# numeric.net
KiCad netlist of a schematic drawn in Altium Designer
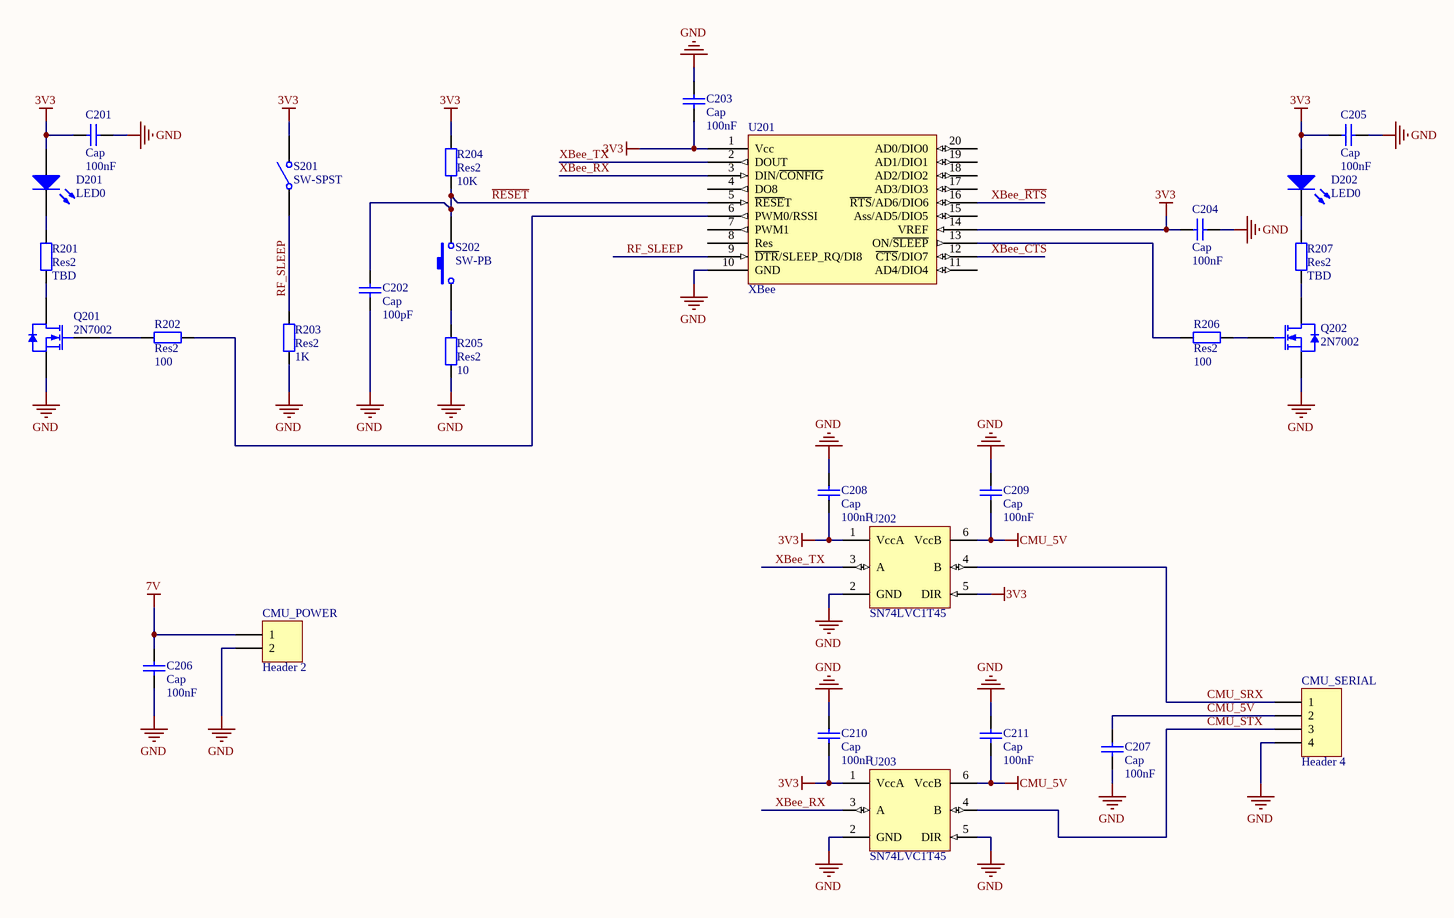
[diagram p0: numeric.SchDoc]

(export (version "E")
  (design (tool "Eeschema 10.0.6"))
  (components
    (comp (ref "C201")
      (value "Cap")
      (footprint "RAD-0.3")
      (description "Capacitor")
      (fields (field (name "ALTIUM_VALUE") "100nF") (field (name "PUBLISHER") "Altium Limited"))
      (libsource (lib "Miscellaneous Devices") (part "Cap"))
    )
    (comp (ref "C202")
      (value "Cap")
      (footprint "RAD-0.3")
      (description "Capacitor")
      (fields (field (name "ALTIUM_VALUE") "100pF") (field (name "PUBLISHER") "Altium Limited"))
      (libsource (lib "Miscellaneous Devices") (part "Cap"))
    )
    (comp (ref "C203")
      (value "Cap")
      (footprint "RAD-0.3")
      (description "Capacitor")
      (fields (field (name "ALTIUM_VALUE") "100nF") (field (name "PUBLISHER") "Altium Limited"))
      (libsource (lib "Miscellaneous Devices") (part "Cap"))
    )
    (comp (ref "C204")
      (value "Cap")
      (footprint "RAD-0.3")
      (description "Capacitor")
      (fields (field (name "ALTIUM_VALUE") "100nF") (field (name "PUBLISHER") "Altium Limited"))
      (libsource (lib "Miscellaneous Devices") (part "Cap"))
    )
    (comp (ref "C205")
      (value "Cap")
      (footprint "RAD-0.3")
      (description "Capacitor")
      (fields (field (name "ALTIUM_VALUE") "100nF") (field (name "PUBLISHER") "Altium Limited"))
      (libsource (lib "Miscellaneous Devices") (part "Cap"))
    )
    (comp (ref "C206")
      (value "Cap")
      (footprint "RAD-0.3")
      (description "Capacitor")
      (fields (field (name "ALTIUM_VALUE") "100nF") (field (name "PUBLISHER") "Altium Limited"))
      (libsource (lib "Miscellaneous Devices") (part "Cap"))
    )
    (comp (ref "C207")
      (value "Cap")
      (footprint "RAD-0.3")
      (description "Capacitor")
      (fields (field (name "ALTIUM_VALUE") "100nF") (field (name "PUBLISHER") "Altium Limited"))
      (libsource (lib "Miscellaneous Devices") (part "Cap"))
    )
    (comp (ref "C208")
      (value "Cap")
      (footprint "RAD-0.3")
      (description "Capacitor")
      (fields (field (name "ALTIUM_VALUE") "100nF") (field (name "PUBLISHER") "Altium Limited"))
      (libsource (lib "Miscellaneous Devices") (part "Cap"))
    )
    (comp (ref "C209")
      (value "Cap")
      (footprint "RAD-0.3")
      (description "Capacitor")
      (fields (field (name "ALTIUM_VALUE") "100nF") (field (name "PUBLISHER") "Altium Limited"))
      (libsource (lib "Miscellaneous Devices") (part "Cap"))
    )
    (comp (ref "C210")
      (value "Cap")
      (footprint "RAD-0.3")
      (description "Capacitor")
      (fields (field (name "ALTIUM_VALUE") "100nF") (field (name "PUBLISHER") "Altium Limited"))
      (libsource (lib "Miscellaneous Devices") (part "Cap"))
    )
    (comp (ref "C211")
      (value "Cap")
      (footprint "RAD-0.3")
      (description "Capacitor")
      (fields (field (name "ALTIUM_VALUE") "100nF") (field (name "PUBLISHER") "Altium Limited"))
      (libsource (lib "Miscellaneous Devices") (part "Cap"))
    )
    (comp (ref "CMU_POWER")
      (value "Header 2")
      (footprint "HDR1X2")
      (description "Header, 2-Pin")
      (fields (field (name "PUBLISHER") "Altium Limited"))
      (libsource (lib "Miscellaneous Connectors") (part "Header 2"))
    )
    (comp (ref "CMU_SERIAL")
      (value "Header 4")
      (footprint "HDR1X4")
      (description "Header, 4-Pin")
      (fields (field (name "PUBLISHER") "Altium Limited"))
      (libsource (lib "Miscellaneous Connectors") (part "Header 4"))
    )
    (comp (ref "D201")
      (value "LED0")
      (footprint "LED-0")
      (description "Typical INFRARED GaAs LED")
      (fields (field (name "PUBLISHER") "Altium Limited"))
      (libsource (lib "Miscellaneous Devices") (part "LED0"))
    )
    (comp (ref "D202")
      (value "LED0")
      (footprint "LED-0")
      (description "Typical INFRARED GaAs LED")
      (fields (field (name "PUBLISHER") "Altium Limited"))
      (libsource (lib "Miscellaneous Devices") (part "LED0"))
    )
    (comp (ref "Q201")
      (value "2N7002")
      (footprint "SOT23_N")
      (description "N-channel Enhancement Mode Field-effect Transistor")
      (fields (field (name "PUBLISHER") "Altium Limited"))
      (libsource (lib "Philips Discrete MOSFET - Low Power") (part "2N7002"))
    )
    (comp (ref "Q202")
      (value "2N7002")
      (footprint "SOT23_N")
      (description "N-channel Enhancement Mode Field-effect Transistor")
      (fields (field (name "PUBLISHER") "Altium Limited"))
      (libsource (lib "Philips Discrete MOSFET - Low Power") (part "2N7002"))
    )
    (comp (ref "R201")
      (value "Res2")
      (footprint "AXIAL-0.4")
      (description "Resistor")
      (fields (field (name "ALTIUM_VALUE") "TBD") (field (name "PUBLISHER") "Altium Limited"))
      (libsource (lib "") (part "Res2_1"))
    )
    (comp (ref "R202")
      (value "Res2")
      (footprint "AXIAL-0.4")
      (description "Resistor")
      (fields (field (name "ALTIUM_VALUE") "100") (field (name "PUBLISHER") "Altium Limited"))
      (libsource (lib "Miscellaneous Devices") (part "Res2"))
    )
    (comp (ref "R203")
      (value "Res2")
      (footprint "AXIAL-0.4")
      (description "Resistor")
      (fields (field (name "ALTIUM_VALUE") "1K") (field (name "PUBLISHER") "Altium Limited"))
      (libsource (lib "") (part "Res2_1"))
    )
    (comp (ref "R204")
      (value "Res2")
      (footprint "AXIAL-0.4")
      (description "Resistor")
      (fields (field (name "ALTIUM_VALUE") "10K") (field (name "PUBLISHER") "Altium Limited"))
      (libsource (lib "") (part "Res2_1"))
    )
    (comp (ref "R205")
      (value "Res2")
      (footprint "AXIAL-0.4")
      (description "Resistor")
      (fields (field (name "ALTIUM_VALUE") "10") (field (name "PUBLISHER") "Altium Limited"))
      (libsource (lib "") (part "Res2_1"))
    )
    (comp (ref "R206")
      (value "Res2")
      (footprint "AXIAL-0.4")
      (description "Resistor")
      (fields (field (name "ALTIUM_VALUE") "100") (field (name "PUBLISHER") "Altium Limited"))
      (libsource (lib "Miscellaneous Devices") (part "Res2"))
    )
    (comp (ref "R207")
      (value "Res2")
      (footprint "AXIAL-0.4")
      (description "Resistor")
      (fields (field (name "ALTIUM_VALUE") "TBD") (field (name "PUBLISHER") "Altium Limited"))
      (libsource (lib "") (part "Res2_1"))
    )
    (comp (ref "S201")
      (value "SW-SPST")
      (footprint "SPST-2")
      (description "Single-Pole, Single-Throw Switch")
      (fields (field (name "PUBLISHER") "Altium Limited"))
      (libsource (lib "Miscellaneous Devices") (part "SW-SPST"))
    )
    (comp (ref "S202")
      (value "SW-PB")
      (footprint "SPST-2")
      (description "Switch")
      (fields (field (name "PUBLISHER") "Altium Limited"))
      (libsource (lib "Miscellaneous Devices") (part "SW-PB"))
    )
    (comp (ref "U201") (value "XBee") (libsource (lib "Oufff_Lib2") (part "XBee")))
    (comp (ref "U202")
      (value "SN74LVC1T45")
      (footprint "1262-01")
      (description "SINGLE-BIT DUAL-SUPPLY BUS TRANSCEIVER  WITH CONFIGURABLE VOLTAGE TRANSLATION AND 3-STATE OUTPUTS")
      (libsource (lib "Oufff_Lib2") (part "SN74LVC1T45"))
    )
    (comp (ref "U203")
      (value "SN74LVC1T45")
      (footprint "1262-01")
      (description "SINGLE-BIT DUAL-SUPPLY BUS TRANSCEIVER  WITH CONFIGURABLE VOLTAGE TRANSLATION AND 3-STATE OUTPUTS")
      (libsource (lib "Oufff_Lib2") (part "SN74LVC1T45"))
    )
  )
  (nets
    (net (code "1") (name "/CMU_SRX") (class "Default")
      (node (ref "CMU_SERIAL") (pin "1") (pinfunction "1_1") (pintype "passive"))
      (node (ref "U202") (pin "4") (pinfunction "B_4") (pintype "bidirectional"))
    )
    (net (code "2") (name "/CMU_STX") (class "Default")
      (node (ref "CMU_SERIAL") (pin "3") (pinfunction "3_3") (pintype "passive"))
      (node (ref "U203") (pin "4") (pinfunction "B_4") (pintype "bidirectional"))
    )
    (net (code "3") (name "/RF_SLEEP") (class "Default")
      (node (ref "R203") (pin "2") (pinfunction "2_2") (pintype "passive"))
      (node (ref "S201") (pin "1") (pinfunction "COMMON_1") (pintype "passive"))
      (node (ref "U201") (pin "9") (pinfunction "~{DTR}/SLEEP_RQ/DI8_9") (pintype "input"))
    )
    (net (code "4") (name "/XBee_RX") (class "Default")
      (node (ref "U201") (pin "3") (pinfunction "DIN/~{CONFIG}_3") (pintype "input"))
      (node (ref "U203") (pin "3") (pinfunction "A_3") (pintype "bidirectional"))
    )
    (net (code "5") (name "/XBee_TX") (class "Default")
      (node (ref "U201") (pin "2") (pinfunction "DOUT_2") (pintype "output"))
      (node (ref "U202") (pin "3") (pinfunction "A_3") (pintype "bidirectional"))
    )
    (net (code "6") (name "/XBee_~{CTS}") (class "Default")
      (node (ref "U201") (pin "12") (pinfunction "~{CTS}/DIO7_12") (pintype "bidirectional"))
    )
    (net (code "7") (name "/XBee_~{RTS}") (class "Default")
      (node (ref "U201") (pin "16") (pinfunction "~{RTS}/AD6/DIO6_16") (pintype "bidirectional"))
    )
    (net (code "8") (name "/~{RESET}") (class "Default")
      (node (ref "C202") (pin "2") (pinfunction "2_2") (pintype "passive"))
      (node (ref "R204") (pin "1") (pinfunction "1_1") (pintype "passive"))
      (node (ref "S202") (pin "2") (pinfunction "2_2") (pintype "passive"))
      (node (ref "U201") (pin "5") (pinfunction "~{RESE}T_5") (pintype "input"))
    )
    (net (code "9") (name "3V3") (class "Default")
      (node (ref "C201") (pin "1") (pinfunction "1_1") (pintype "passive"))
      (node (ref "C203") (pin "1") (pinfunction "1_1") (pintype "passive"))
      (node (ref "C204") (pin "2") (pinfunction "2_2") (pintype "passive"))
      (node (ref "C205") (pin "1") (pinfunction "1_1") (pintype "passive"))
      (node (ref "C208") (pin "1") (pinfunction "1_1") (pintype "passive"))
      (node (ref "C210") (pin "1") (pinfunction "1_1") (pintype "passive"))
      (node (ref "D201") (pin "1") (pinfunction "A_1") (pintype "passive"))
      (node (ref "D202") (pin "1") (pinfunction "A_1") (pintype "passive"))
      (node (ref "R204") (pin "2") (pinfunction "2_2") (pintype "passive"))
      (node (ref "S201") (pin "2") (pinfunction "NO_2") (pintype "passive"))
      (node (ref "U201") (pin "1") (pinfunction "Vcc_1") (pintype "power_in"))
      (node (ref "U201") (pin "14") (pinfunction "VREF_14") (pintype "input"))
      (node (ref "U202") (pin "1") (pinfunction "VccA_1") (pintype "power_in"))
      (node (ref "U202") (pin "5") (pinfunction "DIR_5") (pintype "input"))
      (node (ref "U203") (pin "1") (pinfunction "VccA_1") (pintype "power_in"))
    )
    (net (code "10") (name "7V") (class "Default")
      (node (ref "C206") (pin "2") (pinfunction "2_2") (pintype "passive"))
      (node (ref "CMU_POWER") (pin "1") (pinfunction "1_1") (pintype "passive"))
    )
    (net (code "11") (name "CMU_5V") (class "Default")
      (node (ref "C207") (pin "2") (pinfunction "2_2") (pintype "passive"))
      (node (ref "C209") (pin "1") (pinfunction "1_1") (pintype "passive"))
      (node (ref "C211") (pin "1") (pinfunction "1_1") (pintype "passive"))
      (node (ref "CMU_SERIAL") (pin "2") (pinfunction "2_2") (pintype "passive"))
      (node (ref "U202") (pin "6") (pinfunction "VccB_6") (pintype "power_in"))
      (node (ref "U203") (pin "6") (pinfunction "VccB_6") (pintype "power_in"))
    )
    (net (code "12") (name "GND") (class "Default")
      (node (ref "C201") (pin "2") (pinfunction "2_2") (pintype "passive"))
      (node (ref "C202") (pin "1") (pinfunction "1_1") (pintype "passive"))
      (node (ref "C203") (pin "2") (pinfunction "2_2") (pintype "passive"))
      (node (ref "C204") (pin "1") (pinfunction "1_1") (pintype "passive"))
      (node (ref "C205") (pin "2") (pinfunction "2_2") (pintype "passive"))
      (node (ref "C206") (pin "1") (pinfunction "1_1") (pintype "passive"))
      (node (ref "C207") (pin "1") (pinfunction "1_1") (pintype "passive"))
      (node (ref "C208") (pin "2") (pinfunction "2_2") (pintype "passive"))
      (node (ref "C209") (pin "2") (pinfunction "2_2") (pintype "passive"))
      (node (ref "C210") (pin "2") (pinfunction "2_2") (pintype "passive"))
      (node (ref "C211") (pin "2") (pinfunction "2_2") (pintype "passive"))
      (node (ref "CMU_POWER") (pin "2") (pinfunction "2_2") (pintype "passive"))
      (node (ref "CMU_SERIAL") (pin "4") (pinfunction "4_4") (pintype "passive"))
      (node (ref "Q201") (pin "2") (pinfunction "S_2") (pintype "passive"))
      (node (ref "Q202") (pin "2") (pinfunction "S_2") (pintype "passive"))
      (node (ref "R203") (pin "1") (pinfunction "1_1") (pintype "passive"))
      (node (ref "R205") (pin "1") (pinfunction "1_1") (pintype "passive"))
      (node (ref "U201") (pin "10") (pinfunction "GND_10") (pintype "power_in"))
      (node (ref "U202") (pin "2") (pinfunction "GND_2") (pintype "power_in"))
      (node (ref "U203") (pin "2") (pinfunction "GND_2") (pintype "power_in"))
      (node (ref "U203") (pin "5") (pinfunction "DIR_5") (pintype "input"))
    )
    (net (code "13") (name "Net-(D201-K)") (class "Default")
      (node (ref "D201") (pin "2") (pinfunction "K_2") (pintype "passive"))
      (node (ref "R201") (pin "2") (pinfunction "2_2") (pintype "passive"))
    )
    (net (code "14") (name "Net-(D202-K)") (class "Default")
      (node (ref "D202") (pin "2") (pinfunction "K_2") (pintype "passive"))
      (node (ref "R207") (pin "2") (pinfunction "2_2") (pintype "passive"))
    )
    (net (code "15") (name "Net-(Q201-D)") (class "Default")
      (node (ref "Q201") (pin "3") (pinfunction "D_3") (pintype "passive"))
      (node (ref "R201") (pin "1") (pinfunction "1_1") (pintype "passive"))
    )
    (net (code "16") (name "Net-(Q201-G)") (class "Default")
      (node (ref "Q201") (pin "1") (pinfunction "G_1") (pintype "passive"))
      (node (ref "R202") (pin "1") (pinfunction "1_1") (pintype "passive"))
    )
    (net (code "17") (name "Net-(Q202-D)") (class "Default")
      (node (ref "Q202") (pin "3") (pinfunction "D_3") (pintype "passive"))
      (node (ref "R207") (pin "1") (pinfunction "1_1") (pintype "passive"))
    )
    (net (code "18") (name "Net-(Q202-G)") (class "Default")
      (node (ref "Q202") (pin "1") (pinfunction "G_1") (pintype "passive"))
      (node (ref "R206") (pin "2") (pinfunction "2_2") (pintype "passive"))
    )
    (net (code "19") (name "Net-(R205-Pad2)") (class "Default")
      (node (ref "R205") (pin "2") (pinfunction "2_2") (pintype "passive"))
      (node (ref "S202") (pin "1") (pinfunction "1_1") (pintype "passive"))
    )
    (net (code "20") (name "Net-(U201-ON{slash}~{SLEEP})") (class "Default")
      (node (ref "R206") (pin "1") (pinfunction "1_1") (pintype "passive"))
      (node (ref "U201") (pin "13") (pinfunction "ON/~{SLEEP}_13") (pintype "output"))
    )
    (net (code "21") (name "Net-(U201-PWM0{slash}RSSI)") (class "Default")
      (node (ref "R202") (pin "2") (pinfunction "2_2") (pintype "passive"))
      (node (ref "U201") (pin "6") (pinfunction "PWM0/RSSI_6") (pintype "output"))
    )
    (net (code "22") (name "unconnected-(U201-AD0{slash}DIO0-Pad20)") (class "Default")
      (node (ref "U201") (pin "20") (pinfunction "AD0/DIO0_20") (pintype "bidirectional"))
    )
    (net (code "23") (name "unconnected-(U201-AD1{slash}DIO1-Pad19)") (class "Default")
      (node (ref "U201") (pin "19") (pinfunction "AD1/DIO1_19") (pintype "bidirectional"))
    )
    (net (code "24") (name "unconnected-(U201-AD2{slash}DIO2-Pad18)") (class "Default")
      (node (ref "U201") (pin "18") (pinfunction "AD2/DIO2_18") (pintype "bidirectional"))
    )
    (net (code "25") (name "unconnected-(U201-AD3{slash}DIO3-Pad17)") (class "Default")
      (node (ref "U201") (pin "17") (pinfunction "AD3/DIO3_17") (pintype "bidirectional"))
    )
    (net (code "26") (name "unconnected-(U201-AD4{slash}DIO4-Pad11)") (class "Default")
      (node (ref "U201") (pin "11") (pinfunction "AD4/DIO4_11") (pintype "bidirectional"))
    )
    (net (code "27") (name "unconnected-(U201-Ass{slash}AD5{slash}DIO5-Pad15)") (class "Default")
      (node (ref "U201") (pin "15") (pinfunction "Ass/AD5/DIO5_15") (pintype "bidirectional"))
    )
    (net (code "28") (name "unconnected-(U201-DO8-Pad4)") (class "Default")
      (node (ref "U201") (pin "4") (pinfunction "DO8_4") (pintype "output"))
    )
    (net (code "29") (name "unconnected-(U201-PWM1-Pad7)") (class "Default")
      (node (ref "U201") (pin "7") (pinfunction "PWM1_7") (pintype "output"))
    )
    (net (code "30") (name "unconnected-(U201-Res-Pad8)") (class "Default")
      (node (ref "U201") (pin "8") (pinfunction "Res_8") (pintype "passive"))
    )
  )
)
